# DS3231.net
KiCad netlist of a schematic drawn in Altium Designer
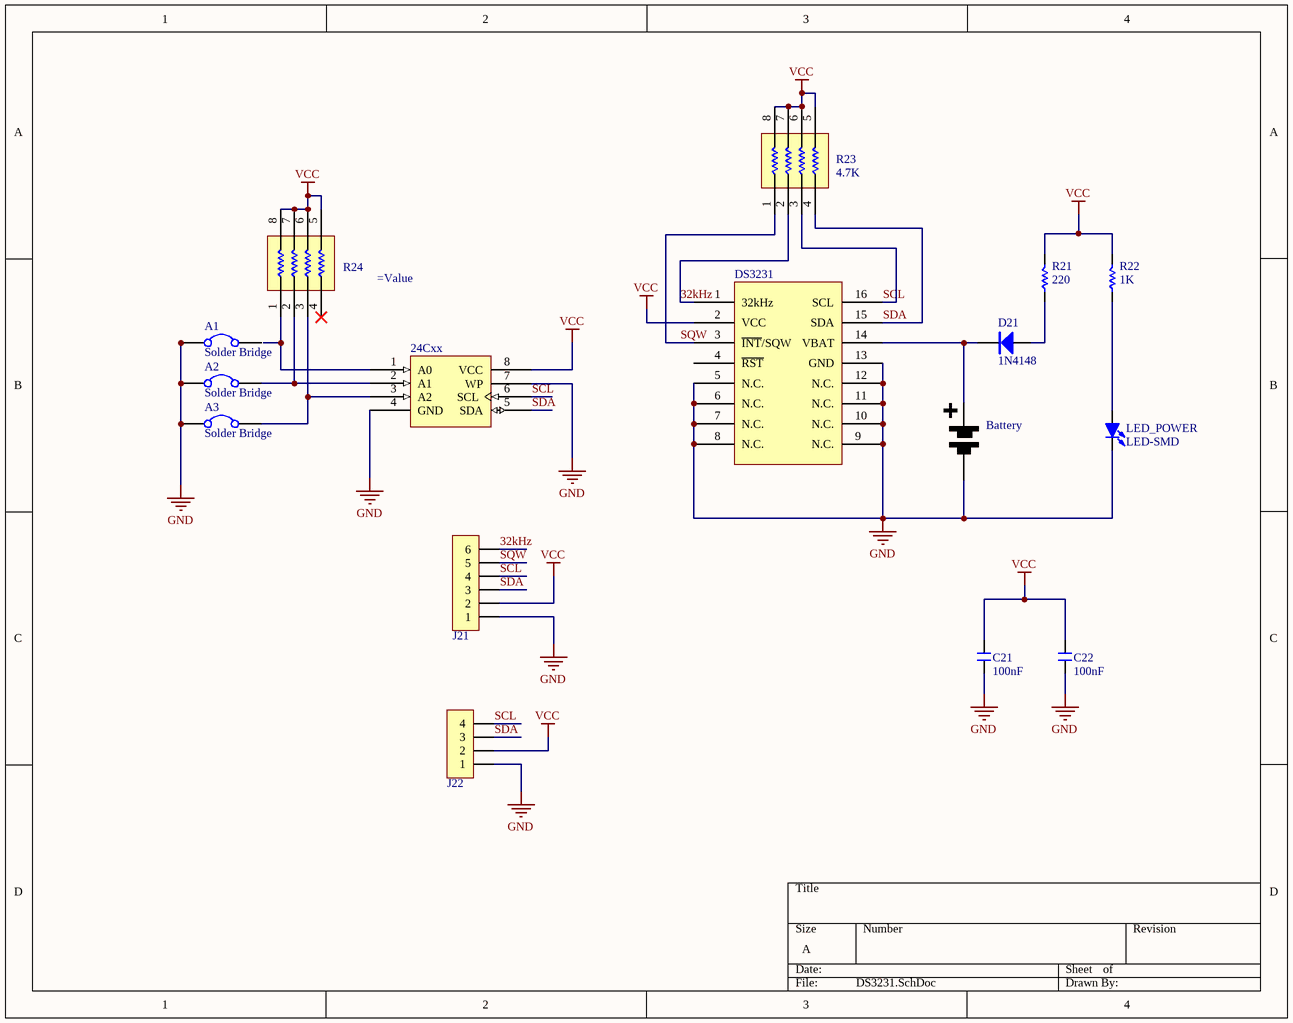
[diagram p0: DS3231.SchDoc]

(export (version "E")
  (design (tool "Eeschema 10.0.6"))
  (components
    (comp (ref "24Cxx")
      (value "24Cxx")
      (footprint "SOP8_L")
      (description "Two-wire Serial EEPROM")
      (fields (field (name "版权归属") "源创客"))
      (libsource (lib "Integrated Circuit") (part "24Cxx"))
    )
    (comp (ref "A1")
      (value "Solder Bridge")
      (footprint "Solder Bridge")
      (libsource (lib "Jumper-SolderBridge") (part "Solder Bridge"))
    )
    (comp (ref "A2")
      (value "Solder Bridge")
      (footprint "Solder Bridge")
      (libsource (lib "Jumper-SolderBridge") (part "Solder Bridge"))
    )
    (comp (ref "A3")
      (value "Solder Bridge")
      (footprint "Solder Bridge")
      (libsource (lib "Jumper-SolderBridge") (part "Solder Bridge"))
    )
    (comp (ref "Battery")
      (value "Battery Button Cell")
      (footprint "CR2032")
      (description "Mini Battery")
      (libsource (lib "Battery Holder") (part "Battery Button Cell"))
    )
    (comp (ref "C21")
      (value "100nF")
      (footprint "C 0805")
      (description "Non-polar patch capacitor")
      (fields (field (name "版权归属") "源创客"))
      (libsource (lib "Passive (Resistor-Capacitor-Inductor-Veristor-Ferrite)") (part "C"))
    )
    (comp (ref "C22")
      (value "100nF")
      (footprint "C 0805")
      (description "Non-polar patch capacitor")
      (fields (field (name "版权归属") "源创客"))
      (libsource (lib "Passive (Resistor-Capacitor-Inductor-Veristor-Ferrite)") (part "C"))
    )
    (comp (ref "D21")
      (value "1N4148")
      (footprint "MINI_MELF (LL34)")
      (description "High speed switching diode")
      (fields (field (name "版权归属") "源创客"))
      (libsource (lib "Diode-Zener-Rectifier Bridge") (part "1N4148"))
    )
    (comp (ref "DS3231")
      (value "DS3231")
      (footprint "SOP16W_L")
      (description "Real time clock chip")
      (libsource (lib "Integrated Circuit") (part "DS3231"))
    )
    (comp (ref "J21")
      (value "HDR-1X6")
      (footprint "HDR-1X6")
      (description "6P接插件")
      (fields (field (name "版权归属") "源创客"))
      (libsource (lib "Connectors") (part "Header 6"))
    )
    (comp (ref "J22")
      (value "HDR-1X4")
      (footprint "HDR-1X4")
      (description "4P connector")
      (fields (field (name "版权归属") "源创客"))
      (libsource (lib "Connectors") (part "Header 4"))
    )
    (comp (ref "LED_POWER")
      (value "LED-SMD")
      (footprint "LED 0805R")
      (description "Patch LED")
      (fields (field (name "版权归属") "源创客"))
      (libsource (lib "LED") (part "LED-SMD"))
    )
    (comp (ref "R21")
      (value "220")
      (footprint "R 0805")
      (description "Chip resistor")
      (fields (field (name "版权归属") "源创客"))
      (libsource (lib "Passive (Resistor-Capacitor-Inductor-Veristor-Ferrite)") (part "R"))
    )
    (comp (ref "R22")
      (value "1K")
      (footprint "R 0805")
      (description "Chip resistor")
      (fields (field (name "版权归属") "源创客"))
      (libsource (lib "Passive (Resistor-Capacitor-Inductor-Veristor-Ferrite)") (part "R"))
    )
    (comp (ref "R23")
      (value "4.7K")
      (footprint "RA1206 (4x0603)")
      (description "4 way Chip Resistor Array")
      (libsource (lib "Passive (Resistor-Capacitor-Inductor-Veristor-Ferrite)") (part "R-ARR"))
    )
    (comp (ref "R24")
      (value "~")
      (footprint "RA1206 (4x0603)")
      (description "4 way Chip Resistor Array")
      (libsource (lib "Passive (Resistor-Capacitor-Inductor-Veristor-Ferrite)") (part "R-ARR"))
    )
  )
  (nets
    (net (code "1") (name "/32kHz") (class "Default")
      (node (ref "DS3231") (pin "1") (pinfunction "32kHz_1") (pintype "passive"))
      (node (ref "J21") (pin "6") (pinfunction "6_6") (pintype "passive"))
      (node (ref "R23") (pin "2") (pinfunction "2_2") (pintype "passive"))
    )
    (net (code "2") (name "/SCL") (class "Default")
      (node (ref "24Cxx") (pin "6") (pinfunction "SCL_6") (pintype "input"))
      (node (ref "DS3231") (pin "16") (pinfunction "SCL_16") (pintype "passive"))
      (node (ref "J21") (pin "4") (pinfunction "4_4") (pintype "passive"))
      (node (ref "J22") (pin "4") (pinfunction "4_4") (pintype "passive"))
      (node (ref "R23") (pin "3") (pinfunction "3_3") (pintype "passive"))
    )
    (net (code "3") (name "/SDA") (class "Default")
      (node (ref "24Cxx") (pin "5") (pinfunction "SDA_5") (pintype "bidirectional"))
      (node (ref "DS3231") (pin "15") (pinfunction "SDA_15") (pintype "passive"))
      (node (ref "J21") (pin "3") (pinfunction "3_3") (pintype "passive"))
      (node (ref "J22") (pin "3") (pinfunction "3_3") (pintype "passive"))
      (node (ref "R23") (pin "4") (pinfunction "4_4") (pintype "passive"))
    )
    (net (code "4") (name "/SQW") (class "Default")
      (node (ref "DS3231") (pin "3") (pinfunction "~{INT}/SQW_3") (pintype "passive"))
      (node (ref "J21") (pin "5") (pinfunction "5_5") (pintype "passive"))
      (node (ref "R23") (pin "1") (pinfunction "1_1") (pintype "passive"))
    )
    (net (code "5") (name "GND") (class "Default")
      (node (ref "24Cxx") (pin "4") (pinfunction "GND_4") (pintype "passive"))
      (node (ref "24Cxx") (pin "7") (pinfunction "WP_7") (pintype "passive"))
      (node (ref "A1") (pin "1") (pinfunction "1_1") (pintype "passive"))
      (node (ref "A2") (pin "1") (pinfunction "1_1") (pintype "passive"))
      (node (ref "A3") (pin "1") (pinfunction "1_1") (pintype "passive"))
      (node (ref "Battery") (pin "2") (pinfunction "-_2") (pintype "passive"))
      (node (ref "C21") (pin "2") (pinfunction "2_2") (pintype "passive"))
      (node (ref "C22") (pin "1") (pinfunction "1_1") (pintype "passive"))
      (node (ref "DS3231") (pin "10") (pinfunction "N.C._10") (pintype "passive"))
      (node (ref "DS3231") (pin "11") (pinfunction "N.C._11") (pintype "passive"))
      (node (ref "DS3231") (pin "12") (pinfunction "N.C._12") (pintype "passive"))
      (node (ref "DS3231") (pin "13") (pinfunction "GND_13") (pintype "passive"))
      (node (ref "DS3231") (pin "5") (pinfunction "N.C._5") (pintype "passive"))
      (node (ref "DS3231") (pin "6") (pinfunction "N.C._6") (pintype "passive"))
      (node (ref "DS3231") (pin "7") (pinfunction "N.C._7") (pintype "passive"))
      (node (ref "DS3231") (pin "8") (pinfunction "N.C._8") (pintype "passive"))
      (node (ref "DS3231") (pin "9") (pinfunction "N.C._9") (pintype "passive"))
      (node (ref "J21") (pin "1") (pinfunction "1_1") (pintype "passive"))
      (node (ref "J22") (pin "1") (pinfunction "1_1") (pintype "passive"))
      (node (ref "LED_POWER") (pin "2") (pinfunction "K_2") (pintype "passive"))
    )
    (net (code "6") (name "Net-(24Cxx-A0)") (class "Default")
      (node (ref "24Cxx") (pin "1") (pinfunction "A0_1") (pintype "input"))
      (node (ref "R24") (pin "1") (pinfunction "1_1") (pintype "passive"))
    )
    (net (code "7") (name "Net-(24Cxx-A1)") (class "Default")
      (node (ref "24Cxx") (pin "2") (pinfunction "A1_2") (pintype "input"))
      (node (ref "A2") (pin "2") (pinfunction "2_2") (pintype "passive"))
      (node (ref "R24") (pin "2") (pinfunction "2_2") (pintype "passive"))
    )
    (net (code "8") (name "Net-(24Cxx-A2)") (class "Default")
      (node (ref "24Cxx") (pin "3") (pinfunction "A2_3") (pintype "input"))
      (node (ref "A3") (pin "2") (pinfunction "2_2") (pintype "passive"))
      (node (ref "R24") (pin "3") (pinfunction "3_3") (pintype "passive"))
    )
    (net (code "9") (name "Net-(Battery-+)") (class "Default")
      (node (ref "Battery") (pin "1") (pinfunction "+_1") (pintype "passive"))
      (node (ref "D21") (pin "2") (pinfunction "K_2") (pintype "passive"))
      (node (ref "DS3231") (pin "14") (pinfunction "VBAT_14") (pintype "passive"))
    )
    (net (code "10") (name "Net-(D21-A)") (class "Default")
      (node (ref "D21") (pin "1") (pinfunction "A_1") (pintype "passive"))
      (node (ref "R21") (pin "1") (pinfunction "1_1") (pintype "passive"))
    )
    (net (code "11") (name "Net-(LED_POWER-A)") (class "Default")
      (node (ref "LED_POWER") (pin "1") (pinfunction "A_1") (pintype "passive"))
      (node (ref "R22") (pin "1") (pinfunction "1_1") (pintype "passive"))
    )
    (net (code "12") (name "VCC") (class "Default")
      (node (ref "24Cxx") (pin "8") (pinfunction "VCC_8") (pintype "power_in"))
      (node (ref "C21") (pin "1") (pinfunction "1_1") (pintype "passive"))
      (node (ref "C22") (pin "2") (pinfunction "2_2") (pintype "passive"))
      (node (ref "DS3231") (pin "2") (pinfunction "VCC_2") (pintype "passive"))
      (node (ref "J21") (pin "2") (pinfunction "2_2") (pintype "passive"))
      (node (ref "J22") (pin "2") (pinfunction "2_2") (pintype "passive"))
      (node (ref "R21") (pin "2") (pinfunction "2_2") (pintype "passive"))
      (node (ref "R22") (pin "2") (pinfunction "2_2") (pintype "passive"))
      (node (ref "R23") (pin "5") (pinfunction "5_5") (pintype "passive"))
      (node (ref "R23") (pin "6") (pinfunction "6_6") (pintype "passive"))
      (node (ref "R23") (pin "7") (pinfunction "7_7") (pintype "passive"))
      (node (ref "R23") (pin "8") (pinfunction "8_8") (pintype "passive"))
      (node (ref "R24") (pin "5") (pinfunction "5_5") (pintype "passive"))
      (node (ref "R24") (pin "6") (pinfunction "6_6") (pintype "passive"))
      (node (ref "R24") (pin "7") (pinfunction "7_7") (pintype "passive"))
      (node (ref "R24") (pin "8") (pinfunction "8_8") (pintype "passive"))
    )
    (net (code "13") (name "unconnected-(A1-Pad2)") (class "Default")
      (node (ref "A1") (pin "2") (pinfunction "2_2") (pintype "passive"))
    )
    (net (code "14") (name "unconnected-(DS3231-~{RST}-Pad4)") (class "Default")
      (node (ref "DS3231") (pin "4") (pinfunction "~{RST}_4") (pintype "passive"))
    )
    (net (code "15") (name "unconnected-(R24-Pad4)") (class "Default")
      (node (ref "R24") (pin "4") (pinfunction "4_4") (pintype "passive+no_connect"))
    )
  )
)
